# L-D5019-05-02.net
KiCad netlist of a schematic drawn in Altium Designer
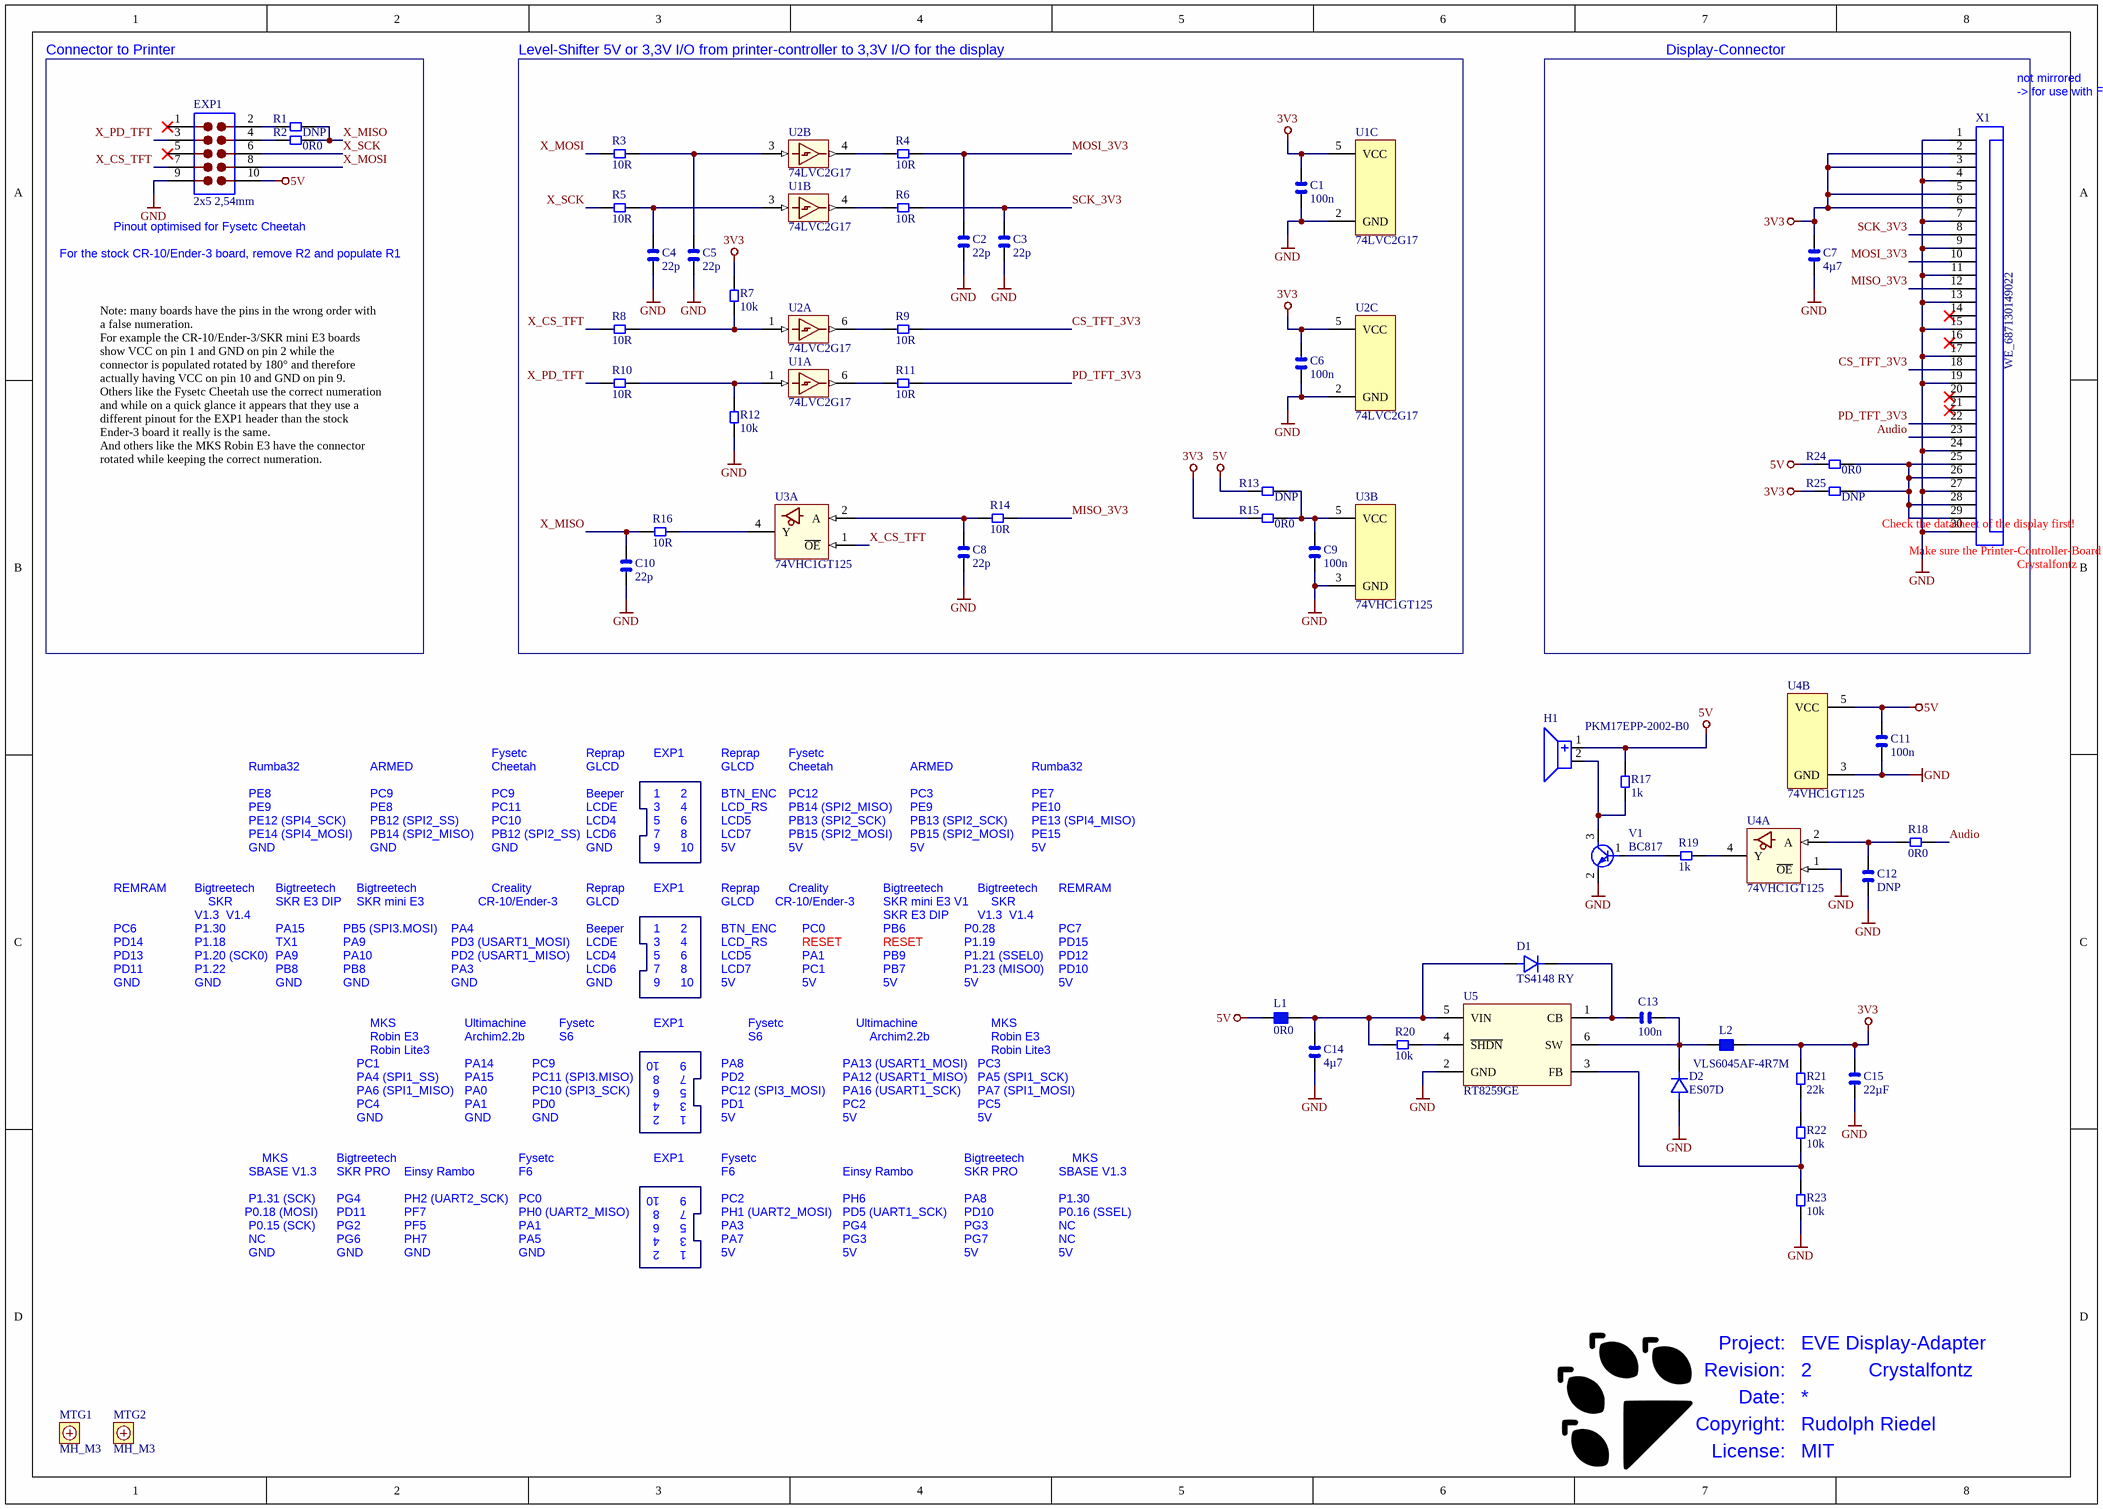
[diagram p0: L-D5019-05-02.SchDoc]

(export (version "E")
  (design (tool "Eeschema 10.0.6"))
  (components
    (comp (ref "C1")
      (value "100n")
      (footprint "CAPC2012X14L")
      (description "0805 Chip Capacitor")
      (fields (field (name "PART NUMBER") "CAPC_0805") (field (name "EDITOR") "rriedel"))
      (libsource (lib "HW-Labor_GF") (part "CAP_2_V2"))
    )
    (comp (ref "C2")
      (value "22p")
      (footprint "CAPC2012X14L")
      (description "0805 Chip Capacitor")
      (fields (field (name "PART NUMBER") "CAPC_0805") (field (name "EDITOR") "rriedel"))
      (libsource (lib "HW-Labor_GF") (part "CAP_2_V2"))
    )
    (comp (ref "C3")
      (value "22p")
      (footprint "CAPC2012X14L")
      (description "0805 Chip Capacitor")
      (fields (field (name "PART NUMBER") "CAPC_0805") (field (name "EDITOR") "rriedel"))
      (libsource (lib "HW-Labor_GF") (part "CAP_2_V2"))
    )
    (comp (ref "C4")
      (value "22p")
      (footprint "CAPC2012X14L")
      (description "0805 Chip Capacitor")
      (fields (field (name "PART NUMBER") "CAPC_0805") (field (name "EDITOR") "rriedel"))
      (libsource (lib "HW-Labor_GF") (part "CAP_2_V2"))
    )
    (comp (ref "C5")
      (value "22p")
      (footprint "CAPC2012X14L")
      (description "0805 Chip Capacitor")
      (fields (field (name "PART NUMBER") "CAPC_0805") (field (name "EDITOR") "rriedel"))
      (libsource (lib "HW-Labor_GF") (part "CAP_2_V2"))
    )
    (comp (ref "C6")
      (value "100n")
      (footprint "CAPC2012X14L")
      (description "0805 Chip Capacitor")
      (fields (field (name "PART NUMBER") "CAPC_0805") (field (name "EDITOR") "rriedel"))
      (libsource (lib "HW-Labor_GF") (part "CAP_2_V2"))
    )
    (comp (ref "C7")
      (value "4µ7")
      (footprint "CAPC2012X14L")
      (description "0805 Chip Capacitor")
      (fields (field (name "PART NUMBER") "CAPC_0805") (field (name "EDITOR") "rriedel"))
      (libsource (lib "HW-Labor_GF") (part "CAP_2_V2"))
    )
    (comp (ref "C8")
      (value "22p")
      (footprint "CAPC2012X14L")
      (description "0805 Chip Capacitor")
      (fields (field (name "PART NUMBER") "CAPC_0805") (field (name "EDITOR") "rriedel"))
      (libsource (lib "HW-Labor_GF") (part "CAP_2_V2"))
    )
    (comp (ref "C9")
      (value "100n")
      (footprint "CAPC2012X14L")
      (description "0805 Chip Capacitor")
      (fields (field (name "PART NUMBER") "CAPC_0805") (field (name "EDITOR") "rriedel"))
      (libsource (lib "HW-Labor_GF") (part "CAP_2_V2"))
    )
    (comp (ref "C10")
      (value "22p")
      (footprint "CAPC2012X14L")
      (description "0805 Chip Capacitor")
      (fields (field (name "PART NUMBER") "CAPC_0805") (field (name "EDITOR") "rriedel"))
      (libsource (lib "HW-Labor_GF") (part "CAP_2_V2"))
    )
    (comp (ref "C11")
      (value "100n")
      (footprint "CAPC2012X14L")
      (description "0805 Chip Capacitor")
      (fields (field (name "PART NUMBER") "CAPC_0805") (field (name "EDITOR") "rriedel"))
      (libsource (lib "HW-Labor_GF") (part "CAP_2_V2"))
    )
    (comp (ref "C12")
      (value "DNP")
      (footprint "CAPC2012X14L")
      (description "0805 Chip Capacitor")
      (fields (field (name "PART NUMBER") "CAPC_0805") (field (name "EDITOR") "rriedel"))
      (libsource (lib "HW-Labor_GF") (part "CAP_2_V2"))
    )
    (comp (ref "C13")
      (value "100n")
      (footprint "CAPC2012X14L")
      (description "0805 Chip Capacitor")
      (fields (field (name "PART NUMBER") "CAPC_0805") (field (name "EDITOR") "rriedel"))
      (libsource (lib "HW-Labor_GF") (part "CAP_2_V2"))
    )
    (comp (ref "C14")
      (value "4µ7")
      (footprint "CAPC2012X14L")
      (description "0805 Chip Capacitor")
      (fields (field (name "PART NUMBER") "CAPC_0805") (field (name "EDITOR") "rriedel"))
      (libsource (lib "HW-Labor_GF") (part "CAP_2_V2"))
    )
    (comp (ref "C15")
      (value "22µF")
      (footprint "CAPC3216X19N")
      (description "1206 Chip Capacitor")
      (fields (field (name "PART NUMBER") "CAPC_1206") (field (name "EDITOR") "rriedel"))
      (libsource (lib "HW-Labor_GF") (part "CAP_2_V2"))
    )
    (comp (ref "D1")
      (value "TS4148 RY")
      (footprint "DIOC2012X10N")
      (description "Small Signal Diode IF 0.3A, VR 75V, 0805")
      (fields
        (field (name "PART NUMBER") "TSC_TS4148 RY")
        (field (name "MANUFACTURER") "TSC")
        (field (name "EDITOR") "rriedel")
      )
      (libsource (lib "HW-Labor_GF") (part "Diode_A2_K1"))
    )
    (comp (ref "D2")
      (value "ES07D")
      (footprint "DIOM2818X11N")
      (description "Ultrafast Rectifier Surface Mount,  IF 0.5A, VR 100V, DO-219AB, AEC-Q101")
      (fields (field (name "MANUFACTURER") "Vishay") (field (name "EDITOR") "rriedel"))
      (libsource (lib "HW-Labor_GF") (part "Diode_A2_K1"))
    )
    (comp (ref "EXP1")
      (value "2x5 2,54mm")
      (footprint "PINH_2x5_2_54mm_shroud")
      (description "Pin-Header 2,54 mm 2x5pins, shrouded")
      (fields (field (name "PART NUMBER") "PINH_2x5_2_54") (field (name "EDITOR") "rriedel"))
      (libsource (lib "HW-Labor_GF") (part "CONM_2x5_V2"))
    )
    (comp (ref "H1")
      (value "PKM17EPP-2002-B0")
      (footprint "Speaker_17mm")
      (description "Speaker, Piezo, THT, dia 17mm,  height 8.6 mm")
      (fields
        (field (name "MANUFACTURER") "Murata")
        (field (name "DISTRIBUTOR_1_PART_NUMBER") "490-4688-ND")
        (field (name "EDITOR") "rriedel")
      )
      (libsource (lib "HW-Labor_GF") (part "Speaker"))
    )
    (comp (ref "L1")
      (value "0R0")
      (footprint "INDC2012X10L")
      (description "0805 Chip Inductor")
      (fields (field (name "PART NUMBER") "INDC_0805") (field (name "EDITOR") "rriedel"))
      (libsource (lib "HW-Labor_GF") (part "IND_2_V1"))
    )
    (comp (ref "L2")
      (value "VLS6045AF-4R7M")
      (footprint "PowerInductor_6x6")
      (description "4,7µH, shielded, 4,7A, 26mR")
      (fields
        (field (name "MANUFACTURER") "TDK")
        (field (name "DISTRIBUTOR_1_PART_NUMBER") "445-180835-1-ND")
        (field (name "EDITOR") "rriedel")
      )
      (libsource (lib "HW-Labor_GF") (part "IND_2_V1"))
    )
    (comp (ref "MTG1")
      (value "MH_M3")
      (footprint "HOLE_3_2MM")
      (description "Mounting-Hole for M3 screws")
      (fields (field (name "EDITOR") "rriedel"))
      (libsource (lib "HW-Labor_GF") (part "MTG_V1"))
    )
    (comp (ref "MTG2")
      (value "MH_M3")
      (footprint "HOLE_3_2MM")
      (description "Mounting-Hole for M3 screws")
      (fields (field (name "EDITOR") "rriedel"))
      (libsource (lib "HW-Labor_GF") (part "MTG_V1"))
    )
    (comp (ref "R1")
      (value "DNP")
      (footprint "RESC2012X06L")
      (description "0805 Chip Resistor")
      (fields (field (name "PART NUMBER") "RESC_0805") (field (name "EDITOR") "rriedel"))
      (libsource (lib "HW-Labor_GF") (part "RES_2_V2"))
    )
    (comp (ref "R2")
      (value "0R0")
      (footprint "RESC2012X06L")
      (description "0805 Chip Resistor")
      (fields (field (name "PART NUMBER") "RESC_0805") (field (name "EDITOR") "rriedel"))
      (libsource (lib "HW-Labor_GF") (part "RES_2_V2"))
    )
    (comp (ref "R3")
      (value "10R")
      (footprint "RESC2012X06L")
      (description "0805 Chip Resistor")
      (fields (field (name "PART NUMBER") "RESC_0805") (field (name "EDITOR") "rriedel"))
      (libsource (lib "HW-Labor_GF") (part "RES_2_V2"))
    )
    (comp (ref "R4")
      (value "10R")
      (footprint "RESC2012X06L")
      (description "0805 Chip Resistor")
      (fields (field (name "PART NUMBER") "RESC_0805") (field (name "EDITOR") "rriedel"))
      (libsource (lib "HW-Labor_GF") (part "RES_2_V2"))
    )
    (comp (ref "R5")
      (value "10R")
      (footprint "RESC2012X06L")
      (description "0805 Chip Resistor")
      (fields (field (name "PART NUMBER") "RESC_0805") (field (name "EDITOR") "rriedel"))
      (libsource (lib "HW-Labor_GF") (part "RES_2_V2"))
    )
    (comp (ref "R6")
      (value "10R")
      (footprint "RESC2012X06L")
      (description "0805 Chip Resistor")
      (fields (field (name "PART NUMBER") "RESC_0805") (field (name "EDITOR") "rriedel"))
      (libsource (lib "HW-Labor_GF") (part "RES_2_V2"))
    )
    (comp (ref "R7")
      (value "10k")
      (footprint "RESC2012X06L")
      (description "0805 Chip Resistor")
      (fields (field (name "PART NUMBER") "RESC_0805") (field (name "EDITOR") "rriedel"))
      (libsource (lib "HW-Labor_GF") (part "RES_2_V2"))
    )
    (comp (ref "R8")
      (value "10R")
      (footprint "RESC2012X06L")
      (description "0805 Chip Resistor")
      (fields (field (name "PART NUMBER") "RESC_0805") (field (name "EDITOR") "rriedel"))
      (libsource (lib "HW-Labor_GF") (part "RES_2_V2"))
    )
    (comp (ref "R9")
      (value "10R")
      (footprint "RESC2012X06L")
      (description "0805 Chip Resistor")
      (fields (field (name "PART NUMBER") "RESC_0805") (field (name "EDITOR") "rriedel"))
      (libsource (lib "HW-Labor_GF") (part "RES_2_V2"))
    )
    (comp (ref "R10")
      (value "10R")
      (footprint "RESC2012X06L")
      (description "0805 Chip Resistor")
      (fields (field (name "PART NUMBER") "RESC_0805") (field (name "EDITOR") "rriedel"))
      (libsource (lib "HW-Labor_GF") (part "RES_2_V2"))
    )
    (comp (ref "R11")
      (value "10R")
      (footprint "RESC2012X06L")
      (description "0805 Chip Resistor")
      (fields (field (name "PART NUMBER") "RESC_0805") (field (name "EDITOR") "rriedel"))
      (libsource (lib "HW-Labor_GF") (part "RES_2_V2"))
    )
    (comp (ref "R12")
      (value "10k")
      (footprint "RESC2012X06L")
      (description "0805 Chip Resistor")
      (fields (field (name "PART NUMBER") "RESC_0805") (field (name "EDITOR") "rriedel"))
      (libsource (lib "HW-Labor_GF") (part "RES_2_V2"))
    )
    (comp (ref "R13")
      (value "DNP")
      (footprint "RESC2012X06L")
      (description "0805 Chip Resistor")
      (fields (field (name "PART NUMBER") "RESC_0805") (field (name "EDITOR") "rriedel"))
      (libsource (lib "HW-Labor_GF") (part "RES_2_V2"))
    )
    (comp (ref "R14")
      (value "10R")
      (footprint "RESC2012X06L")
      (description "0805 Chip Resistor")
      (fields (field (name "PART NUMBER") "RESC_0805") (field (name "EDITOR") "rriedel"))
      (libsource (lib "HW-Labor_GF") (part "RES_2_V2"))
    )
    (comp (ref "R15")
      (value "0R0")
      (footprint "RESC2012X06L")
      (description "0805 Chip Resistor")
      (fields (field (name "PART NUMBER") "RESC_0805") (field (name "EDITOR") "rriedel"))
      (libsource (lib "HW-Labor_GF") (part "RES_2_V2"))
    )
    (comp (ref "R16")
      (value "10R")
      (footprint "RESC2012X06L")
      (description "0805 Chip Resistor")
      (fields (field (name "PART NUMBER") "RESC_0805") (field (name "EDITOR") "rriedel"))
      (libsource (lib "HW-Labor_GF") (part "RES_2_V2"))
    )
    (comp (ref "R17")
      (value "1k")
      (footprint "RESC2012X06L")
      (description "0805 Chip Resistor")
      (fields (field (name "PART NUMBER") "RESC_0805") (field (name "EDITOR") "rriedel"))
      (libsource (lib "HW-Labor_GF") (part "RES_2_V2"))
    )
    (comp (ref "R18")
      (value "0R0")
      (footprint "RESC2012X06L")
      (description "0805 Chip Resistor")
      (fields (field (name "PART NUMBER") "RESC_0805") (field (name "EDITOR") "rriedel"))
      (libsource (lib "HW-Labor_GF") (part "RES_2_V2"))
    )
    (comp (ref "R19")
      (value "1k")
      (footprint "RESC2012X06L")
      (description "0805 Chip Resistor")
      (fields (field (name "PART NUMBER") "RESC_0805") (field (name "EDITOR") "rriedel"))
      (libsource (lib "HW-Labor_GF") (part "RES_2_V2"))
    )
    (comp (ref "R20")
      (value "10k")
      (footprint "RESC2012X06L")
      (description "0805 Chip Resistor")
      (fields (field (name "PART NUMBER") "RESC_0805") (field (name "EDITOR") "rriedel"))
      (libsource (lib "HW-Labor_GF") (part "RES_2_V2"))
    )
    (comp (ref "R21")
      (value "22k")
      (footprint "RESC2012X06L")
      (description "0805 Chip Resistor")
      (fields (field (name "PART NUMBER") "RESC_0805") (field (name "EDITOR") "rriedel"))
      (libsource (lib "HW-Labor_GF") (part "RES_2_V2"))
    )
    (comp (ref "R22")
      (value "10k")
      (footprint "RESC2012X06L")
      (description "0805 Chip Resistor")
      (fields (field (name "PART NUMBER") "RESC_0805") (field (name "EDITOR") "rriedel"))
      (libsource (lib "HW-Labor_GF") (part "RES_2_V2"))
    )
    (comp (ref "R23")
      (value "10k")
      (footprint "RESC2012X06L")
      (description "0805 Chip Resistor")
      (fields (field (name "PART NUMBER") "RESC_0805") (field (name "EDITOR") "rriedel"))
      (libsource (lib "HW-Labor_GF") (part "RES_2_V2"))
    )
    (comp (ref "R24")
      (value "0R0")
      (footprint "RESC2012X06L")
      (description "0805 Chip Resistor")
      (fields (field (name "PART NUMBER") "RESC_0805") (field (name "EDITOR") "rriedel"))
      (libsource (lib "HW-Labor_GF") (part "RES_2_V2"))
    )
    (comp (ref "R25")
      (value "DNP")
      (footprint "RESC2012X06L")
      (description "0805 Chip Resistor")
      (fields (field (name "PART NUMBER") "RESC_0805") (field (name "EDITOR") "rriedel"))
      (libsource (lib "HW-Labor_GF") (part "RES_2_V2"))
    )
    (comp (ref "U1")
      (value "74LVC2G17")
      (footprint "SOT95P280X110-6N")
      (description "Dual Schmitt-Trigger Buffer with 5.5V tolerant inputs")
      (fields
        (field (name "MANUFACTURER") "TI")
        (field (name "DISTRIBUTOR_1_PART_NUMBER") "296-SN74LVC2G17DBVRCT-ND‎")
        (field (name "EDITOR") "rriedel")
      )
      (libsource (lib "HW-Labor_GF") (part "74LVC2G17"))
    )
    (comp (ref "U2")
      (value "74LVC2G17")
      (footprint "SOT95P280X110-6N")
      (description "Dual Schmitt-Trigger Buffer with 5.5V tolerant inputs")
      (fields
        (field (name "MANUFACTURER") "TI")
        (field (name "DISTRIBUTOR_1_PART_NUMBER") "296-SN74LVC2G17DBVRCT-ND‎")
        (field (name "EDITOR") "rriedel")
      )
      (libsource (lib "HW-Labor_GF") (part "74LVC2G17"))
    )
    (comp (ref "U3")
      (value "74VHC1GT125")
      (footprint "SOT95P280X110-5N")
      (description "1x Buffer with OE; 3-state,Level Shifter 3,3V to 5V and 5V to 3.3V")
      (fields
        (field (name "MANUFACTURER") "ON Semiconductor")
        (field (name "DISTRIBUTOR_1_PART_NUMBER") "1703291")
        (field (name "EDITOR") "rriedel")
      )
      (libsource (lib "HW-Labor_GF") (part "74LVC1G125G"))
    )
    (comp (ref "U4")
      (value "74VHC1GT125")
      (footprint "SOT95P280X110-5N")
      (description "1x Buffer with OE; 3-state,Level Shifter 3,3V to 5V and 5V to 3.3V")
      (fields
        (field (name "MANUFACTURER") "ON Semiconductor")
        (field (name "DISTRIBUTOR_1_PART_NUMBER") "1703291")
        (field (name "EDITOR") "rriedel")
      )
      (libsource (lib "") (part "74LVC1G125G_1"))
    )
    (comp (ref "U5")
      (value "RT8259GE")
      (footprint "SOT95P280X110-6N")
      (description "Step-Down DC/DC Regulator, 24V, 1.2A, 1,4MHz")
      (fields
        (field (name "MANUFACTURER") "Richtek")
        (field (name "DISTRIBUTOR_1_PART_NUMBER") "1028-1497-1-ND")
        (field (name "EDITOR") "rriedel")
      )
      (libsource (lib "HW-Labor_GF") (part "StepDown_SOT23-6"))
    )
    (comp (ref "V1")
      (value "BC817")
      (footprint "SOT95P280X110-3N")
      (description "NPN Transistor SOT23, 1=B, 2=C, 3=E")
      (fields (field (name "EDITOR") "rriedel"))
      (libsource (lib "HW-Labor_GF") (part "NPN_B1_C2_E3"))
    )
    (comp (ref "X1")
      (value "WE_687130149022")
      (footprint "WE_687130149022")
      (description "30pin WR-FPC 0.50 mm SMT ZIF Horizontal - Bottom Contact")
      (fields
        (field (name "MANUFACTURER") "Wuerth")
        (field (name "DISTRIBUTOR_1_PART_NUMBER") "732-6007-1-ND")
        (field (name "EDITOR") "rriedel")
      )
      (libsource (lib "HW-Labor_GF") (part "FPC_30"))
    )
  )
  (nets
    (net (code "1") (name "/Audio") (class "Default")
      (node (ref "R18") (pin "2") (pinfunction "2_2") (pintype "passive"))
      (node (ref "X1") (pin "23") (pinfunction "23_23") (pintype "passive"))
    )
    (net (code "2") (name "/CS_TFT_3V3") (class "Default")
      (node (ref "R9") (pin "2") (pinfunction "2_2") (pintype "passive"))
      (node (ref "X1") (pin "18") (pinfunction "18_18") (pintype "passive"))
    )
    (net (code "3") (name "/MISO_3V3") (class "Default")
      (node (ref "R14") (pin "2") (pinfunction "2_2") (pintype "passive"))
      (node (ref "X1") (pin "12") (pinfunction "12_12") (pintype "passive"))
    )
    (net (code "4") (name "/MOSI_3V3") (class "Default")
      (node (ref "C2") (pin "2") (pinfunction "2_2") (pintype "passive"))
      (node (ref "R4") (pin "2") (pinfunction "2_2") (pintype "passive"))
      (node (ref "X1") (pin "10") (pinfunction "10_10") (pintype "passive"))
    )
    (net (code "5") (name "/PD_TFT_3V3") (class "Default")
      (node (ref "R11") (pin "2") (pinfunction "2_2") (pintype "passive"))
      (node (ref "X1") (pin "22") (pinfunction "22_22") (pintype "passive"))
    )
    (net (code "6") (name "/SCK_3V3") (class "Default")
      (node (ref "C3") (pin "2") (pinfunction "2_2") (pintype "passive"))
      (node (ref "R6") (pin "2") (pinfunction "2_2") (pintype "passive"))
      (node (ref "X1") (pin "8") (pinfunction "8_8") (pintype "passive"))
    )
    (net (code "7") (name "/X_CS_TFT") (class "Default")
      (node (ref "EXP1") (pin "7") (pinfunction "7_7") (pintype "passive"))
      (node (ref "R8") (pin "1") (pinfunction "1_1") (pintype "passive"))
      (node (ref "U3") (pin "1") (pinfunction "~{OE}_1") (pintype "input"))
    )
    (net (code "8") (name "/X_MISO") (class "Default")
      (node (ref "C10") (pin "2") (pinfunction "2_2") (pintype "passive"))
      (node (ref "R1") (pin "2") (pinfunction "2_2") (pintype "passive"))
      (node (ref "R16") (pin "1") (pinfunction "1_1") (pintype "passive"))
      (node (ref "R2") (pin "2") (pinfunction "2_2") (pintype "passive"))
    )
    (net (code "9") (name "/X_MOSI") (class "Default")
      (node (ref "EXP1") (pin "8") (pinfunction "8_8") (pintype "passive"))
      (node (ref "R3") (pin "1") (pinfunction "1_1") (pintype "passive"))
    )
    (net (code "10") (name "/X_PD_TFT") (class "Default")
      (node (ref "EXP1") (pin "3") (pinfunction "3_3") (pintype "passive"))
      (node (ref "R10") (pin "1") (pinfunction "1_1") (pintype "passive"))
    )
    (net (code "11") (name "/X_SCK") (class "Default")
      (node (ref "EXP1") (pin "6") (pinfunction "6_6") (pintype "passive"))
      (node (ref "R5") (pin "1") (pinfunction "1_1") (pintype "passive"))
    )
    (net (code "12") (name "3V3") (class "Default")
      (node (ref "C1") (pin "2") (pinfunction "2_2") (pintype "passive"))
      (node (ref "C15") (pin "2") (pinfunction "2_2") (pintype "passive"))
      (node (ref "C6") (pin "2") (pinfunction "2_2") (pintype "passive"))
      (node (ref "C7") (pin "2") (pinfunction "2_2") (pintype "passive"))
      (node (ref "L2") (pin "2") (pinfunction "2_2") (pintype "passive"))
      (node (ref "R15") (pin "1") (pinfunction "1_1") (pintype "passive"))
      (node (ref "R21") (pin "2") (pinfunction "2_2") (pintype "passive"))
      (node (ref "R25") (pin "1") (pinfunction "1_1") (pintype "passive"))
      (node (ref "R7") (pin "2") (pinfunction "2_2") (pintype "passive"))
      (node (ref "U1") (pin "5") (pinfunction "VCC_5") (pintype "power_in"))
      (node (ref "U2") (pin "5") (pinfunction "VCC_5") (pintype "power_in"))
      (node (ref "X1") (pin "2") (pinfunction "2_2") (pintype "passive"))
      (node (ref "X1") (pin "3") (pinfunction "3_3") (pintype "passive"))
      (node (ref "X1") (pin "5") (pinfunction "5_5") (pintype "passive"))
      (node (ref "X1") (pin "6") (pinfunction "6_6") (pintype "passive"))
    )
    (net (code "13") (name "5V") (class "Default")
      (node (ref "C11") (pin "2") (pinfunction "2_2") (pintype "passive"))
      (node (ref "EXP1") (pin "10") (pinfunction "10_10") (pintype "passive"))
      (node (ref "H1") (pin "1") (pinfunction "1_1") (pintype "passive"))
      (node (ref "L1") (pin "1") (pinfunction "1_1") (pintype "passive"))
      (node (ref "R13") (pin "1") (pinfunction "1_1") (pintype "passive"))
      (node (ref "R17") (pin "2") (pinfunction "2_2") (pintype "passive"))
      (node (ref "R24") (pin "1") (pinfunction "1_1") (pintype "passive"))
      (node (ref "U4") (pin "5") (pinfunction "VCC_5") (pintype "passive"))
    )
    (net (code "14") (name "GND") (class "Default")
      (node (ref "C1") (pin "1") (pinfunction "1_1") (pintype "passive"))
      (node (ref "C10") (pin "1") (pinfunction "1_1") (pintype "passive"))
      (node (ref "C11") (pin "1") (pinfunction "1_1") (pintype "passive"))
      (node (ref "C12") (pin "1") (pinfunction "1_1") (pintype "passive"))
      (node (ref "C14") (pin "1") (pinfunction "1_1") (pintype "passive"))
      (node (ref "C15") (pin "1") (pinfunction "1_1") (pintype "passive"))
      (node (ref "C2") (pin "1") (pinfunction "1_1") (pintype "passive"))
      (node (ref "C3") (pin "1") (pinfunction "1_1") (pintype "passive"))
      (node (ref "C4") (pin "1") (pinfunction "1_1") (pintype "passive"))
      (node (ref "C5") (pin "1") (pinfunction "1_1") (pintype "passive"))
      (node (ref "C6") (pin "1") (pinfunction "1_1") (pintype "passive"))
      (node (ref "C7") (pin "1") (pinfunction "1_1") (pintype "passive"))
      (node (ref "C8") (pin "1") (pinfunction "1_1") (pintype "passive"))
      (node (ref "C9") (pin "1") (pinfunction "1_1") (pintype "passive"))
      (node (ref "D2") (pin "2") (pinfunction "2_2") (pintype "passive"))
      (node (ref "EXP1") (pin "9") (pinfunction "9_9") (pintype "passive"))
      (node (ref "R12") (pin "1") (pinfunction "1_1") (pintype "passive"))
      (node (ref "R23") (pin "1") (pinfunction "1_1") (pintype "passive"))
      (node (ref "U1") (pin "2") (pinfunction "GND_2") (pintype "power_in"))
      (node (ref "U2") (pin "2") (pinfunction "GND_2") (pintype "power_in"))
      (node (ref "U3") (pin "3") (pinfunction "GND_3") (pintype "passive"))
      (node (ref "U4") (pin "1") (pinfunction "~{OE}_1") (pintype "input"))
      (node (ref "U4") (pin "3") (pinfunction "GND_3") (pintype "passive"))
      (node (ref "U5") (pin "2") (pinfunction "GND_2") (pintype "power_in"))
      (node (ref "V1") (pin "2") (pinfunction "2_2") (pintype "passive"))
      (node (ref "X1") (pin "1") (pinfunction "1_1") (pintype "passive"))
      (node (ref "X1") (pin "11") (pinfunction "11_11") (pintype "passive"))
      (node (ref "X1") (pin "13") (pinfunction "13_13") (pintype "passive"))
      (node (ref "X1") (pin "15") (pinfunction "15_15") (pintype "passive"))
      (node (ref "X1") (pin "17") (pinfunction "17_17") (pintype "passive"))
      (node (ref "X1") (pin "19") (pinfunction "19_19") (pintype "passive"))
      (node (ref "X1") (pin "24") (pinfunction "24_24") (pintype "passive"))
      (node (ref "X1") (pin "27") (pinfunction "27_27") (pintype "passive"))
      (node (ref "X1") (pin "30") (pinfunction "30_30") (pintype "passive"))
      (node (ref "X1") (pin "4") (pinfunction "4_4") (pintype "passive"))
      (node (ref "X1") (pin "7") (pinfunction "7_7") (pintype "passive"))
      (node (ref "X1") (pin "9") (pinfunction "9_9") (pintype "passive"))
    )
    (net (code "15") (name "Net-(EXP1-Pad2)") (class "Default")
      (node (ref "EXP1") (pin "2") (pinfunction "2_2") (pintype "passive"))
      (node (ref "R1") (pin "1") (pinfunction "1_1") (pintype "passive"))
    )
    (net (code "16") (name "Net-(EXP1-Pad4)") (class "Default")
      (node (ref "EXP1") (pin "4") (pinfunction "4_4") (pintype "passive"))
      (node (ref "R2") (pin "1") (pinfunction "1_1") (pintype "passive"))
    )
    (net (code "17") (name "Net-(H1-Pad2)") (class "Default")
      (node (ref "H1") (pin "2") (pinfunction "2_2") (pintype "passive"))
      (node (ref "R17") (pin "1") (pinfunction "1_1") (pintype "passive"))
      (node (ref "V1") (pin "3") (pinfunction "3_3") (pintype "passive"))
    )
    (net (code "18") (name "Net-(R19-Pad2)") (class "Default")
      (node (ref "R19") (pin "2") (pinfunction "2_2") (pintype "passive"))
      (node (ref "V1") (pin "1") (pinfunction "1_1") (pintype "passive"))
    )
    (net (code "19") (name "Net-(R21-Pad1)") (class "Default")
      (node (ref "R21") (pin "1") (pinfunction "1_1") (pintype "passive"))
      (node (ref "R22") (pin "2") (pinfunction "2_2") (pintype "passive"))
    )
    (net (code "20") (name "Net-(R24-Pad2)") (class "Default")
      (node (ref "R24") (pin "2") (pinfunction "2_2") (pintype "passive"))
      (node (ref "R25") (pin "2") (pinfunction "2_2") (pintype "passive"))
      (node (ref "X1") (pin "25") (pinfunction "25_25") (pintype "passive"))
      (node (ref "X1") (pin "26") (pinfunction "26_26") (pintype "passive"))
      (node (ref "X1") (pin "28") (pinfunction "28_28") (pintype "passive"))
      (node (ref "X1") (pin "29") (pinfunction "29_29") (pintype "passive"))
    )
    (net (code "21") (name "Net-(U1A-1A)") (class "Default")
      (node (ref "R10") (pin "2") (pinfunction "2_2") (pintype "passive"))
      (node (ref "R12") (pin "2") (pinfunction "2_2") (pintype "passive"))
      (node (ref "U1") (pin "1") (pinfunction "1A_1") (pintype "input"))
    )
    (net (code "22") (name "Net-(U1A-1Y)") (class "Default")
      (node (ref "R11") (pin "1") (pinfunction "1_1") (pintype "passive"))
      (node (ref "U1") (pin "6") (pinfunction "1Y_6") (pintype "output"))
    )
    (net (code "23") (name "Net-(U1B-2A)") (class "Default")
      (node (ref "C4") (pin "2") (pinfunction "2_2") (pintype "passive"))
      (node (ref "R5") (pin "2") (pinfunction "2_2") (pintype "passive"))
      (node (ref "U1") (pin "3") (pinfunction "2A_3") (pintype "input"))
    )
    (net (code "24") (name "Net-(U1B-2Y)") (class "Default")
      (node (ref "R6") (pin "1") (pinfunction "1_1") (pintype "passive"))
      (node (ref "U1") (pin "4") (pinfunction "2Y_4") (pintype "output"))
    )
    (net (code "25") (name "Net-(U2A-1A)") (class "Default")
      (node (ref "R7") (pin "1") (pinfunction "1_1") (pintype "passive"))
      (node (ref "R8") (pin "2") (pinfunction "2_2") (pintype "passive"))
      (node (ref "U2") (pin "1") (pinfunction "1A_1") (pintype "input"))
    )
    (net (code "26") (name "Net-(U2A-1Y)") (class "Default")
      (node (ref "R9") (pin "1") (pinfunction "1_1") (pintype "passive"))
      (node (ref "U2") (pin "6") (pinfunction "1Y_6") (pintype "output"))
    )
    (net (code "27") (name "Net-(U2B-2A)") (class "Default")
      (node (ref "C5") (pin "2") (pinfunction "2_2") (pintype "passive"))
      (node (ref "R3") (pin "2") (pinfunction "2_2") (pintype "passive"))
      (node (ref "U2") (pin "3") (pinfunction "2A_3") (pintype "input"))
    )
    (net (code "28") (name "Net-(U2B-2Y)") (class "Default")
      (node (ref "R4") (pin "1") (pinfunction "1_1") (pintype "passive"))
      (node (ref "U2") (pin "4") (pinfunction "2Y_4") (pintype "output"))
    )
    (net (code "29") (name "Net-(U3A-A)") (class "Default")
      (node (ref "C8") (pin "2") (pinfunction "2_2") (pintype "passive"))
      (node (ref "R14") (pin "1") (pinfunction "1_1") (pintype "passive"))
      (node (ref "U3") (pin "2") (pinfunction "A_2") (pintype "input"))
    )
    (net (code "30") (name "Net-(U3A-Y)") (class "Default")
      (node (ref "R16") (pin "2") (pinfunction "2_2") (pintype "passive"))
      (node (ref "U3") (pin "4") (pinfunction "Y_4") (pintype "tri_state"))
    )
    (net (code "31") (name "Net-(U3B-VCC)") (class "Default")
      (node (ref "C9") (pin "2") (pinfunction "2_2") (pintype "passive"))
      (node (ref "R13") (pin "2") (pinfunction "2_2") (pintype "passive"))
      (node (ref "R15") (pin "2") (pinfunction "2_2") (pintype "passive"))
      (node (ref "U3") (pin "5") (pinfunction "VCC_5") (pintype "passive"))
    )
    (net (code "32") (name "Net-(U4A-A)") (class "Default")
      (node (ref "C12") (pin "2") (pinfunction "2_2") (pintype "passive"))
      (node (ref "R18") (pin "1") (pinfunction "1_1") (pintype "passive"))
      (node (ref "U4") (pin "2") (pinfunction "A_2") (pintype "input"))
    )
    (net (code "33") (name "Net-(U4A-Y)") (class "Default")
      (node (ref "R19") (pin "1") (pinfunction "1_1") (pintype "passive"))
      (node (ref "U4") (pin "4") (pinfunction "Y_4") (pintype "tri_state"))
    )
    (net (code "34") (name "Net-(U5-CB)") (class "Default")
      (node (ref "C13") (pin "1") (pinfunction "1_1") (pintype "passive"))
      (node (ref "D1") (pin "1") (pinfunction "1_1") (pintype "passive"))
      (node (ref "U5") (pin "1") (pinfunction "CB_1") (pintype "passive"))
    )
    (net (code "35") (name "Net-(U5-FB)") (class "Default")
      (node (ref "R22") (pin "1") (pinfunction "1_1") (pintype "passive"))
      (node (ref "R23") (pin "2") (pinfunction "2_2") (pintype "passive"))
      (node (ref "U5") (pin "3") (pinfunction "FB_3") (pintype "passive"))
    )
    (net (code "36") (name "Net-(U5-SW)") (class "Default")
      (node (ref "C13") (pin "2") (pinfunction "2_2") (pintype "passive"))
      (node (ref "D2") (pin "1") (pinfunction "1_1") (pintype "passive"))
      (node (ref "L2") (pin "1") (pinfunction "1_1") (pintype "passive"))
      (node (ref "U5") (pin "6") (pinfunction "SW_6") (pintype "passive"))
    )
    (net (code "37") (name "Net-(U5-VIN)") (class "Default")
      (node (ref "C14") (pin "2") (pinfunction "2_2") (pintype "passive"))
      (node (ref "D1") (pin "2") (pinfunction "2_2") (pintype "passive"))
      (node (ref "L1") (pin "2") (pinfunction "2_2") (pintype "passive"))
      (node (ref "R20") (pin "1") (pinfunction "1_1") (pintype "passive"))
      (node (ref "U5") (pin "5") (pinfunction "VIN_5") (pintype "power_in"))
    )
    (net (code "38") (name "Net-(U5-~{SHDN})") (class "Default")
      (node (ref "R20") (pin "2") (pinfunction "2_2") (pintype "passive"))
      (node (ref "U5") (pin "4") (pinfunction "~{SHDN}_4") (pintype "passive"))
    )
    (net (code "39") (name "unconnected-(EXP1-Pad1)") (class "Default")
      (node (ref "EXP1") (pin "1") (pinfunction "1_1") (pintype "passive+no_connect"))
    )
    (net (code "40") (name "unconnected-(EXP1-Pad5)") (class "Default")
      (node (ref "EXP1") (pin "5") (pinfunction "5_5") (pintype "passive+no_connect"))
    )
    (net (code "41") (name "unconnected-(X1-Pad14)") (class "Default")
      (node (ref "X1") (pin "14") (pinfunction "14_14") (pintype "passive+no_connect"))
    )
    (net (code "42") (name "unconnected-(X1-Pad16)") (class "Default")
      (node (ref "X1") (pin "16") (pinfunction "16_16") (pintype "passive+no_connect"))
    )
    (net (code "43") (name "unconnected-(X1-Pad20)") (class "Default")
      (node (ref "X1") (pin "20") (pinfunction "20_20") (pintype "passive+no_connect"))
    )
    (net (code "44") (name "unconnected-(X1-Pad21)") (class "Default")
      (node (ref "X1") (pin "21") (pinfunction "21_21") (pintype "passive+no_connect"))
    )
  )
)
